# untitled.net
KiCad netlist of a schematic drawn in EAGLE
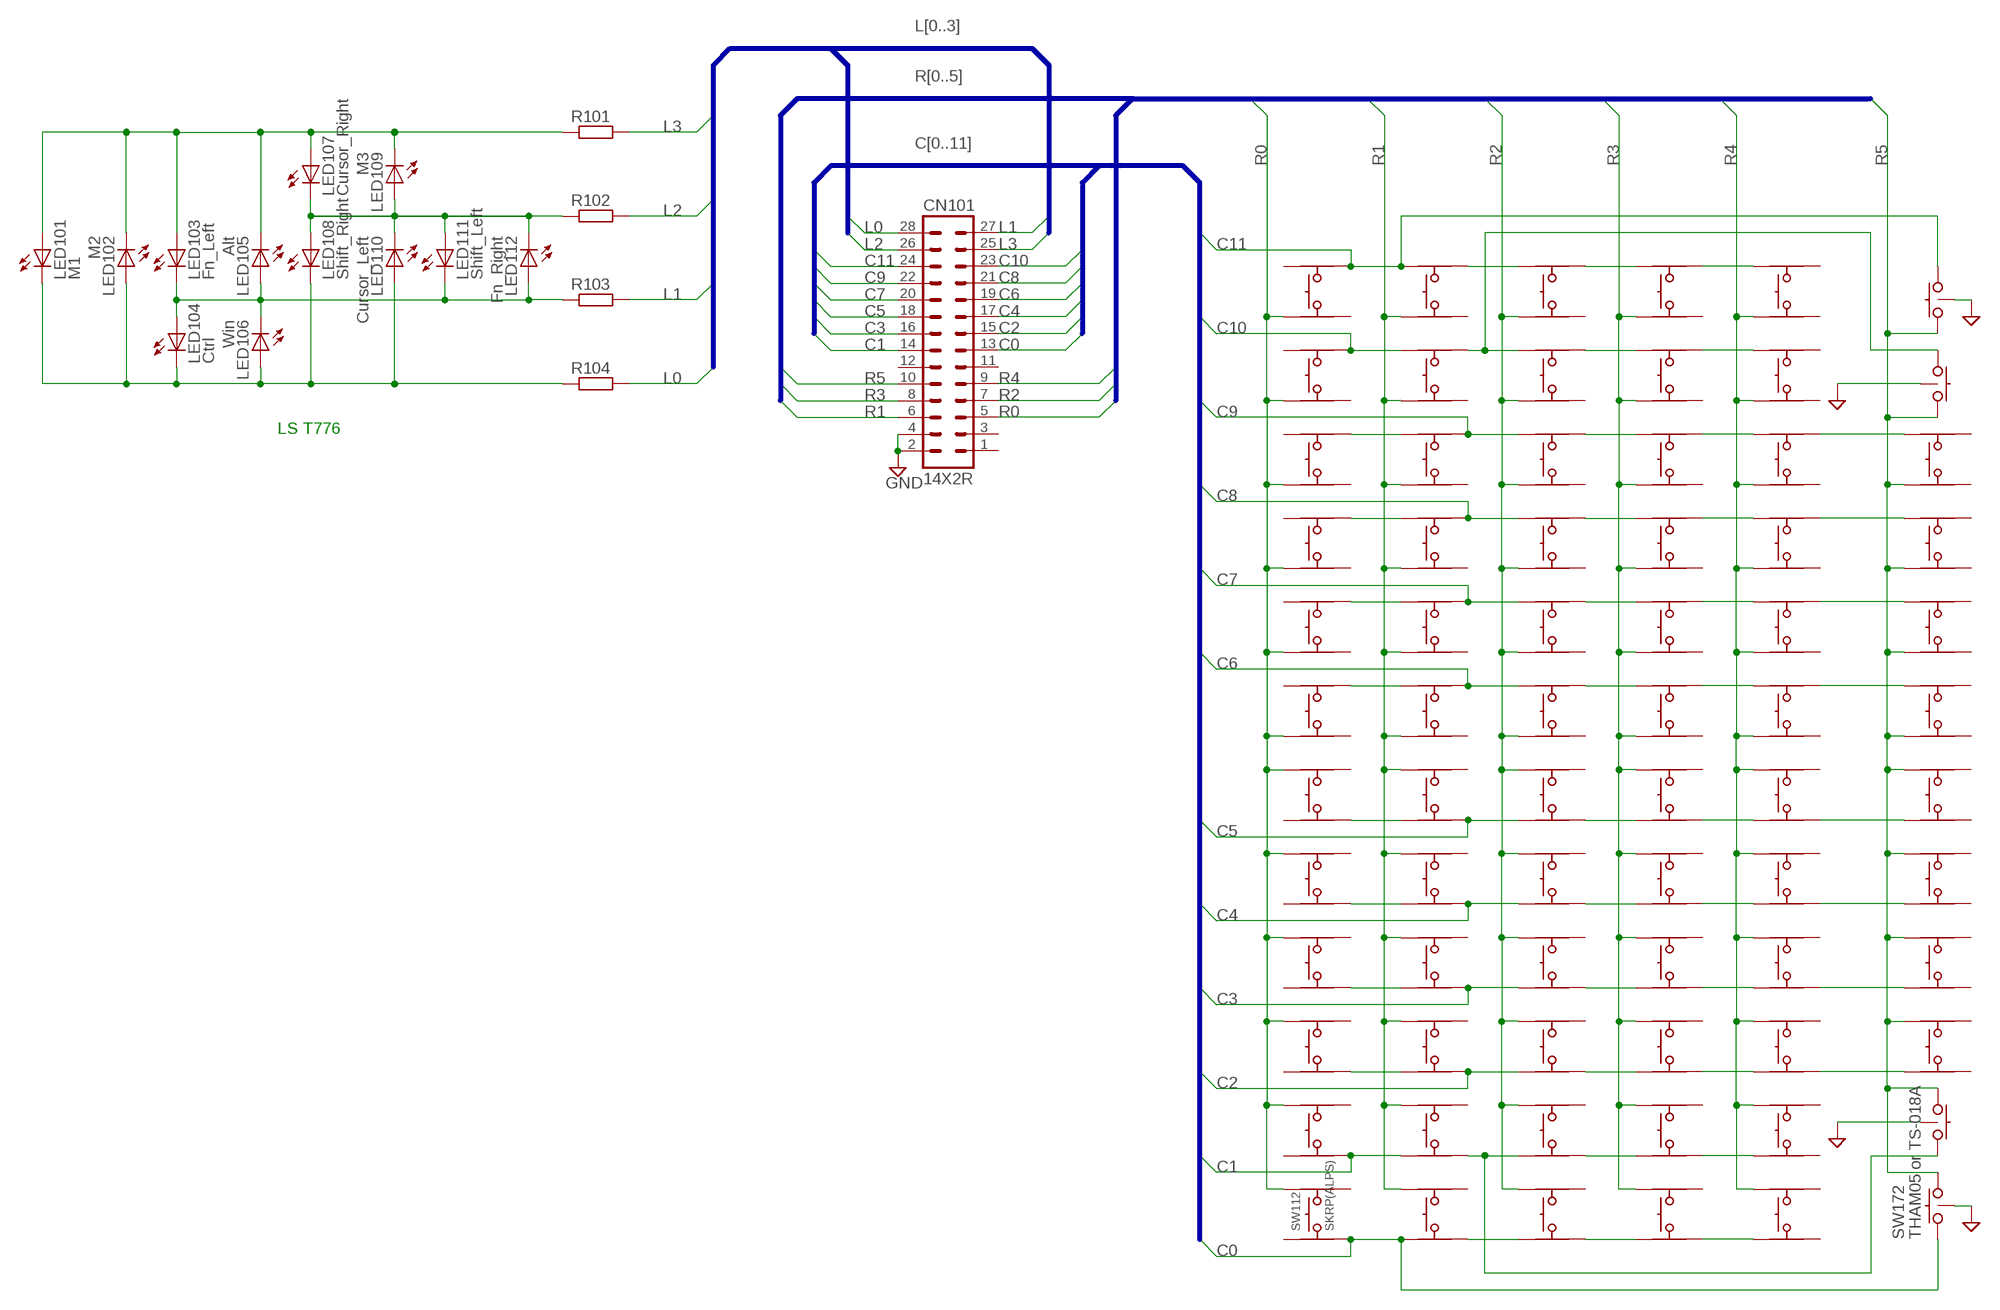
[diagram p0: schematic, sheet 1]

(export (version "E")
  (design (tool "Eeschema 10.0.6"))
  (components
    (comp (ref "CN101")
      (value "14X2R")
      (footprint "eagle-import:2MM_14X2_R")
      (libsource (lib "eagle-import") (part "14X2R"))
    )
    (comp (ref "LED101")
      (value "M1")
      (footprint "eagle-import:P-LCC-2-TOPLED-RG-WINDOW")
      (libsource (lib "eagle-import") (part "LEDP-LCC-2-BACK-W"))
    )
    (comp (ref "LED102")
      (value "M2")
      (footprint "eagle-import:P-LCC-2-TOPLED-RG-WINDOW")
      (libsource (lib "eagle-import") (part "LEDP-LCC-2-BACK-W"))
    )
    (comp (ref "LED103")
      (value "Fn_Left")
      (footprint "eagle-import:P-LCC-2-TOPLED-RG-WINDOW")
      (libsource (lib "eagle-import") (part "LEDP-LCC-2-BACK-W"))
    )
    (comp (ref "LED104")
      (value "Ctrl")
      (footprint "eagle-import:P-LCC-2-TOPLED-RG-WINDOW")
      (libsource (lib "eagle-import") (part "LEDP-LCC-2-BACK-W"))
    )
    (comp (ref "LED105")
      (value "Alt")
      (footprint "eagle-import:P-LCC-2-TOPLED-RG-WINDOW")
      (libsource (lib "eagle-import") (part "LEDP-LCC-2-BACK-W"))
    )
    (comp (ref "LED106")
      (value "Win")
      (footprint "eagle-import:P-LCC-2-TOPLED-RG-WINDOW")
      (libsource (lib "eagle-import") (part "LEDP-LCC-2-BACK-W"))
    )
    (comp (ref "LED107")
      (value "Cursor_Right")
      (footprint "eagle-import:P-LCC-2-TOPLED-RG-WINDOW")
      (libsource (lib "eagle-import") (part "LEDP-LCC-2-BACK-W"))
    )
    (comp (ref "LED108")
      (value "Shift_Right")
      (footprint "eagle-import:P-LCC-2-TOPLED-RG-WINDOW")
      (libsource (lib "eagle-import") (part "LEDP-LCC-2-BACK-W"))
    )
    (comp (ref "LED109")
      (value "M3")
      (footprint "eagle-import:P-LCC-2-TOPLED-RG-WINDOW")
      (libsource (lib "eagle-import") (part "LEDP-LCC-2-BACK-W"))
    )
    (comp (ref "LED110")
      (value "Cursor_Left")
      (footprint "eagle-import:P-LCC-2-TOPLED-RG-WINDOW")
      (libsource (lib "eagle-import") (part "LEDP-LCC-2-BACK-W"))
    )
    (comp (ref "LED111")
      (value "Shift_Left")
      (footprint "eagle-import:P-LCC-2-TOPLED-RG-WINDOW")
      (libsource (lib "eagle-import") (part "LEDP-LCC-2-BACK-W"))
    )
    (comp (ref "LED112")
      (value "Fn_Right")
      (footprint "eagle-import:P-LCC-2-TOPLED-RG-WINDOW")
      (libsource (lib "eagle-import") (part "LEDP-LCC-2-BACK-W"))
    )
    (comp (ref "R101")
      (value "R-EU_R0402-SS")
      (footprint "eagle-import:R0402-SS")
      (libsource (lib "eagle-import") (part "R-EU_R0402-SS"))
    )
    (comp (ref "R102")
      (value "R-EU_R0402-SS")
      (footprint "eagle-import:R0402-SS")
      (libsource (lib "eagle-import") (part "R-EU_R0402-SS"))
    )
    (comp (ref "R103")
      (value "R-EU_R0402-SS")
      (footprint "eagle-import:R0402-SS")
      (libsource (lib "eagle-import") (part "R-EU_R0402-SS"))
    )
    (comp (ref "R104")
      (value "R-EU_R0402-SS")
      (footprint "eagle-import:R0402-SS")
      (libsource (lib "eagle-import") (part "R-EU_R0402-SS"))
    )
    (comp (ref "SW101")
      (value "SW_4PTVAU10-025")
      (footprint "eagle-import:TVAU10-025")
      (libsource (lib "eagle-import") (part "SW_4PTVAU10-025"))
    )
    (comp (ref "SW102")
      (value "SW_4PTVAU10-025")
      (footprint "eagle-import:TVAU10-025")
      (libsource (lib "eagle-import") (part "SW_4PTVAU10-025"))
    )
    (comp (ref "SW103")
      (value "SW_4PTVAU10-025")
      (footprint "eagle-import:TVAU10-025")
      (libsource (lib "eagle-import") (part "SW_4PTVAU10-025"))
    )
    (comp (ref "SW104")
      (value "SW_4PTVAU10-025")
      (footprint "eagle-import:TVAU10-025")
      (libsource (lib "eagle-import") (part "SW_4PTVAU10-025"))
    )
    (comp (ref "SW105")
      (value "SW_4PTVAU10-025")
      (footprint "eagle-import:TVAU10-025")
      (libsource (lib "eagle-import") (part "SW_4PTVAU10-025"))
    )
    (comp (ref "SW106")
      (value "SW_4PTVAU10-025")
      (footprint "eagle-import:TVAU10-025")
      (libsource (lib "eagle-import") (part "SW_4PTVAU10-025"))
    )
    (comp (ref "SW107")
      (value "SW_4PTVAU10-025")
      (footprint "eagle-import:TVAU10-025")
      (libsource (lib "eagle-import") (part "SW_4PTVAU10-025"))
    )
    (comp (ref "SW108")
      (value "SW_4PTVAU10-025")
      (footprint "eagle-import:TVAU10-025")
      (libsource (lib "eagle-import") (part "SW_4PTVAU10-025"))
    )
    (comp (ref "SW109")
      (value "SW_4PTVAU10-025")
      (footprint "eagle-import:TVAU10-025")
      (libsource (lib "eagle-import") (part "SW_4PTVAU10-025"))
    )
    (comp (ref "SW110")
      (value "SW_4PTVAU10-025")
      (footprint "eagle-import:TVAU10-025")
      (libsource (lib "eagle-import") (part "SW_4PTVAU10-025"))
    )
    (comp (ref "SW111")
      (value "SW_4PTVAU10-025")
      (footprint "eagle-import:TVAU10-025")
      (libsource (lib "eagle-import") (part "SW_4PTVAU10-025"))
    )
    (comp (ref "SW112")
      (value "SKRP(ALPS)")
      (footprint "eagle-import:TVAU10-025")
      (libsource (lib "eagle-import") (part "SW_4PTVAU10-025"))
    )
    (comp (ref "SW113")
      (value "SW_4PTVAU10-025")
      (footprint "eagle-import:TVAU10-025")
      (libsource (lib "eagle-import") (part "SW_4PTVAU10-025"))
    )
    (comp (ref "SW114")
      (value "SW_4PTVAU10-025")
      (footprint "eagle-import:TVAU10-025")
      (libsource (lib "eagle-import") (part "SW_4PTVAU10-025"))
    )
    (comp (ref "SW115")
      (value "SW_4PTVAU10-025")
      (footprint "eagle-import:TVAU10-025")
      (libsource (lib "eagle-import") (part "SW_4PTVAU10-025"))
    )
    (comp (ref "SW116")
      (value "SW_4PTVAU10-025")
      (footprint "eagle-import:TVAU10-025")
      (libsource (lib "eagle-import") (part "SW_4PTVAU10-025"))
    )
    (comp (ref "SW117")
      (value "SW_4PTVAU10-025")
      (footprint "eagle-import:TVAU10-025")
      (libsource (lib "eagle-import") (part "SW_4PTVAU10-025"))
    )
    (comp (ref "SW118")
      (value "SW_4PTVAU10-025")
      (footprint "eagle-import:TVAU10-025")
      (libsource (lib "eagle-import") (part "SW_4PTVAU10-025"))
    )
    (comp (ref "SW119")
      (value "SW_4PTVAU10-025")
      (footprint "eagle-import:TVAU10-025")
      (libsource (lib "eagle-import") (part "SW_4PTVAU10-025"))
    )
    (comp (ref "SW120")
      (value "SW_4PTVAU10-025")
      (footprint "eagle-import:TVAU10-025")
      (libsource (lib "eagle-import") (part "SW_4PTVAU10-025"))
    )
    (comp (ref "SW121")
      (value "SW_4PTVAU10-025")
      (footprint "eagle-import:TVAU10-025")
      (libsource (lib "eagle-import") (part "SW_4PTVAU10-025"))
    )
    (comp (ref "SW122")
      (value "SW_4PTVAU10-025")
      (footprint "eagle-import:TVAU10-025")
      (libsource (lib "eagle-import") (part "SW_4PTVAU10-025"))
    )
    (comp (ref "SW123")
      (value "SW_4PTVAU10-025")
      (footprint "eagle-import:TVAU10-025")
      (libsource (lib "eagle-import") (part "SW_4PTVAU10-025"))
    )
    (comp (ref "SW124")
      (value "SW_4PTVAU10-025")
      (footprint "eagle-import:TVAU10-025")
      (libsource (lib "eagle-import") (part "SW_4PTVAU10-025"))
    )
    (comp (ref "SW125")
      (value "SW_4PTVAU10-025")
      (footprint "eagle-import:TVAU10-025")
      (libsource (lib "eagle-import") (part "SW_4PTVAU10-025"))
    )
    (comp (ref "SW126")
      (value "SW_4PTVAU10-025")
      (footprint "eagle-import:TVAU10-025")
      (libsource (lib "eagle-import") (part "SW_4PTVAU10-025"))
    )
    (comp (ref "SW127")
      (value "SW_4PTVAU10-025")
      (footprint "eagle-import:TVAU10-025")
      (libsource (lib "eagle-import") (part "SW_4PTVAU10-025"))
    )
    (comp (ref "SW128")
      (value "SW_4PTVAU10-025")
      (footprint "eagle-import:TVAU10-025")
      (libsource (lib "eagle-import") (part "SW_4PTVAU10-025"))
    )
    (comp (ref "SW129")
      (value "SW_4PTVAU10-025")
      (footprint "eagle-import:TVAU10-025")
      (libsource (lib "eagle-import") (part "SW_4PTVAU10-025"))
    )
    (comp (ref "SW130")
      (value "SW_4PTVAU10-025")
      (footprint "eagle-import:TVAU10-025")
      (libsource (lib "eagle-import") (part "SW_4PTVAU10-025"))
    )
    (comp (ref "SW131")
      (value "SW_4PTVAU10-025")
      (footprint "eagle-import:TVAU10-025")
      (libsource (lib "eagle-import") (part "SW_4PTVAU10-025"))
    )
    (comp (ref "SW132")
      (value "SW_4PTVAU10-025")
      (footprint "eagle-import:TVAU10-025")
      (libsource (lib "eagle-import") (part "SW_4PTVAU10-025"))
    )
    (comp (ref "SW133")
      (value "SW_4PTVAU10-025")
      (footprint "eagle-import:TVAU10-025")
      (libsource (lib "eagle-import") (part "SW_4PTVAU10-025"))
    )
    (comp (ref "SW134")
      (value "SW_4PTVAU10-025")
      (footprint "eagle-import:TVAU10-025")
      (libsource (lib "eagle-import") (part "SW_4PTVAU10-025"))
    )
    (comp (ref "SW135")
      (value "SW_4PTVAU10-025")
      (footprint "eagle-import:TVAU10-025")
      (libsource (lib "eagle-import") (part "SW_4PTVAU10-025"))
    )
    (comp (ref "SW136")
      (value "SW_4PTVAU10-025")
      (footprint "eagle-import:TVAU10-025")
      (libsource (lib "eagle-import") (part "SW_4PTVAU10-025"))
    )
    (comp (ref "SW137")
      (value "SW_4PTVAU10-025")
      (footprint "eagle-import:TVAU10-025")
      (libsource (lib "eagle-import") (part "SW_4PTVAU10-025"))
    )
    (comp (ref "SW138")
      (value "SW_4PTVAU10-025")
      (footprint "eagle-import:TVAU10-025")
      (libsource (lib "eagle-import") (part "SW_4PTVAU10-025"))
    )
    (comp (ref "SW139")
      (value "SW_4PTVAU10-025")
      (footprint "eagle-import:TVAU10-025")
      (libsource (lib "eagle-import") (part "SW_4PTVAU10-025"))
    )
    (comp (ref "SW140")
      (value "SW_4PTVAU10-025")
      (footprint "eagle-import:TVAU10-025")
      (libsource (lib "eagle-import") (part "SW_4PTVAU10-025"))
    )
    (comp (ref "SW141")
      (value "SW_4PTVAU10-025")
      (footprint "eagle-import:TVAU10-025")
      (libsource (lib "eagle-import") (part "SW_4PTVAU10-025"))
    )
    (comp (ref "SW142")
      (value "SW_4PTVAU10-025")
      (footprint "eagle-import:TVAU10-025")
      (libsource (lib "eagle-import") (part "SW_4PTVAU10-025"))
    )
    (comp (ref "SW143")
      (value "SW_4PTVAU10-025")
      (footprint "eagle-import:TVAU10-025")
      (libsource (lib "eagle-import") (part "SW_4PTVAU10-025"))
    )
    (comp (ref "SW144")
      (value "SW_4PTVAU10-025")
      (footprint "eagle-import:TVAU10-025")
      (libsource (lib "eagle-import") (part "SW_4PTVAU10-025"))
    )
    (comp (ref "SW145")
      (value "SW_4PTVAU10-025")
      (footprint "eagle-import:TVAU10-025")
      (libsource (lib "eagle-import") (part "SW_4PTVAU10-025"))
    )
    (comp (ref "SW146")
      (value "SW_4PTVAU10-025")
      (footprint "eagle-import:TVAU10-025")
      (libsource (lib "eagle-import") (part "SW_4PTVAU10-025"))
    )
    (comp (ref "SW147")
      (value "SW_4PTVAU10-025")
      (footprint "eagle-import:TVAU10-025")
      (libsource (lib "eagle-import") (part "SW_4PTVAU10-025"))
    )
    (comp (ref "SW148")
      (value "SW_4PTVAU10-025")
      (footprint "eagle-import:TVAU10-025")
      (libsource (lib "eagle-import") (part "SW_4PTVAU10-025"))
    )
    (comp (ref "SW149")
      (value "SW_4PTVAU10-025")
      (footprint "eagle-import:TVAU10-025")
      (libsource (lib "eagle-import") (part "SW_4PTVAU10-025"))
    )
    (comp (ref "SW150")
      (value "SW_4PTVAU10-025")
      (footprint "eagle-import:TVAU10-025")
      (libsource (lib "eagle-import") (part "SW_4PTVAU10-025"))
    )
    (comp (ref "SW151")
      (value "SW_4PTVAU10-025")
      (footprint "eagle-import:TVAU10-025")
      (libsource (lib "eagle-import") (part "SW_4PTVAU10-025"))
    )
    (comp (ref "SW152")
      (value "SW_4PTVAU10-025")
      (footprint "eagle-import:TVAU10-025")
      (libsource (lib "eagle-import") (part "SW_4PTVAU10-025"))
    )
    (comp (ref "SW153")
      (value "SW_4PTVAU10-025")
      (footprint "eagle-import:TVAU10-025")
      (libsource (lib "eagle-import") (part "SW_4PTVAU10-025"))
    )
    (comp (ref "SW154")
      (value "SW_4PTVAU10-025")
      (footprint "eagle-import:TVAU10-025")
      (libsource (lib "eagle-import") (part "SW_4PTVAU10-025"))
    )
    (comp (ref "SW155")
      (value "SW_4PTVAU10-025")
      (footprint "eagle-import:TVAU10-025")
      (libsource (lib "eagle-import") (part "SW_4PTVAU10-025"))
    )
    (comp (ref "SW156")
      (value "SW_4PTVAU10-025")
      (footprint "eagle-import:TVAU10-025")
      (libsource (lib "eagle-import") (part "SW_4PTVAU10-025"))
    )
    (comp (ref "SW157")
      (value "SW_4PTVAU10-025")
      (footprint "eagle-import:TVAU10-025")
      (libsource (lib "eagle-import") (part "SW_4PTVAU10-025"))
    )
    (comp (ref "SW158")
      (value "SW_4PTVAU10-025")
      (footprint "eagle-import:TVAU10-025")
      (libsource (lib "eagle-import") (part "SW_4PTVAU10-025"))
    )
    (comp (ref "SW159")
      (value "SW_4PTVAU10-025")
      (footprint "eagle-import:TVAU10-025")
      (libsource (lib "eagle-import") (part "SW_4PTVAU10-025"))
    )
    (comp (ref "SW160")
      (value "SW_4PTVAU10-025")
      (footprint "eagle-import:TVAU10-025")
      (libsource (lib "eagle-import") (part "SW_4PTVAU10-025"))
    )
    (comp (ref "SW161")
      (value "SW_WITH_EARTHX")
      (footprint "eagle-import:THAM05")
      (libsource (lib "eagle-import") (part "SW_WITH_EARTHX"))
    )
    (comp (ref "SW162")
      (value "SW_WITH_EARTHX")
      (footprint "eagle-import:THAM05")
      (libsource (lib "eagle-import") (part "SW_WITH_EARTHX"))
    )
    (comp (ref "SW163")
      (value "SW_4PTVAU10-025")
      (footprint "eagle-import:TVAU10-025")
      (libsource (lib "eagle-import") (part "SW_4PTVAU10-025"))
    )
    (comp (ref "SW164")
      (value "SW_4PTVAU10-025")
      (footprint "eagle-import:TVAU10-025")
      (libsource (lib "eagle-import") (part "SW_4PTVAU10-025"))
    )
    (comp (ref "SW165")
      (value "SW_4PTVAU10-025")
      (footprint "eagle-import:TVAU10-025")
      (libsource (lib "eagle-import") (part "SW_4PTVAU10-025"))
    )
    (comp (ref "SW166")
      (value "SW_4PTVAU10-025")
      (footprint "eagle-import:TVAU10-025")
      (libsource (lib "eagle-import") (part "SW_4PTVAU10-025"))
    )
    (comp (ref "SW167")
      (value "SW_4PTVAU10-025")
      (footprint "eagle-import:TVAU10-025")
      (libsource (lib "eagle-import") (part "SW_4PTVAU10-025"))
    )
    (comp (ref "SW168")
      (value "SW_4PTVAU10-025")
      (footprint "eagle-import:TVAU10-025")
      (libsource (lib "eagle-import") (part "SW_4PTVAU10-025"))
    )
    (comp (ref "SW169")
      (value "SW_4PTVAU10-025")
      (footprint "eagle-import:TVAU10-025")
      (libsource (lib "eagle-import") (part "SW_4PTVAU10-025"))
    )
    (comp (ref "SW170")
      (value "SW_4PTVAU10-025")
      (footprint "eagle-import:TVAU10-025")
      (libsource (lib "eagle-import") (part "SW_4PTVAU10-025"))
    )
    (comp (ref "SW171")
      (value "SW_WITH_EARTHX")
      (footprint "eagle-import:THAM05")
      (libsource (lib "eagle-import") (part "SW_WITH_EARTHX"))
    )
    (comp (ref "SW172")
      (value "THAM05 or TS-018A")
      (footprint "eagle-import:THAM05")
      (libsource (lib "eagle-import") (part "SW_WITH_EARTHX"))
    )
  )
  (nets
    (net (code "1") (name "/C0") (class "Default")
      (node (ref "CN101") (pin "13") (pinfunction "13_13") (pintype "passive"))
      (node (ref "SW112") (pin "P$2") (pinfunction "=A_P$2") (pintype "bidirectional"))
      (node (ref "SW124") (pin "P$1") (pinfunction "A_P$1") (pintype "bidirectional"))
      (node (ref "SW172") (pin "P$1") (pinfunction "P$1_P$1") (pintype "passive"))
    )
    (net (code "2") (name "/C1") (class "Default")
      (node (ref "CN101") (pin "14") (pinfunction "14_14") (pintype "passive"))
      (node (ref "SW111") (pin "P$2") (pinfunction "=A_P$2") (pintype "bidirectional"))
      (node (ref "SW123") (pin "P$1") (pinfunction "A_P$1") (pintype "bidirectional"))
    )
    (net (code "3") (name "/C2") (class "Default")
      (node (ref "CN101") (pin "15") (pinfunction "15_15") (pintype "passive"))
      (node (ref "SW122") (pin "P$2") (pinfunction "=A_P$2") (pintype "bidirectional"))
      (node (ref "SW134") (pin "P$1") (pinfunction "A_P$1") (pintype "bidirectional"))
    )
    (net (code "4") (name "/C3") (class "Default")
      (node (ref "CN101") (pin "16") (pinfunction "16_16") (pintype "passive"))
      (node (ref "SW121") (pin "P$2") (pinfunction "=A_P$2") (pintype "bidirectional"))
      (node (ref "SW133") (pin "P$1") (pinfunction "A_P$1") (pintype "bidirectional"))
    )
    (net (code "5") (name "/C4") (class "Default")
      (node (ref "CN101") (pin "17") (pinfunction "17_17") (pintype "passive"))
      (node (ref "SW120") (pin "P$2") (pinfunction "=A_P$2") (pintype "bidirectional"))
      (node (ref "SW132") (pin "P$1") (pinfunction "A_P$1") (pintype "bidirectional"))
    )
    (net (code "6") (name "/C5") (class "Default")
      (node (ref "CN101") (pin "18") (pinfunction "18_18") (pintype "passive"))
      (node (ref "SW119") (pin "P$2") (pinfunction "=A_P$2") (pintype "bidirectional"))
      (node (ref "SW131") (pin "P$1") (pinfunction "A_P$1") (pintype "bidirectional"))
    )
    (net (code "7") (name "/C6") (class "Default")
      (node (ref "CN101") (pin "19") (pinfunction "19_19") (pintype "passive"))
      (node (ref "SW118") (pin "P$4") (pinfunction "=B_P$4") (pintype "bidirectional"))
      (node (ref "SW130") (pin "P$3") (pinfunction "B_P$3") (pintype "bidirectional"))
    )
    (net (code "8") (name "/C7") (class "Default")
      (node (ref "CN101") (pin "20") (pinfunction "20_20") (pintype "passive"))
      (node (ref "SW117") (pin "P$4") (pinfunction "=B_P$4") (pintype "bidirectional"))
      (node (ref "SW129") (pin "P$3") (pinfunction "B_P$3") (pintype "bidirectional"))
    )
    (net (code "9") (name "/C8") (class "Default")
      (node (ref "CN101") (pin "21") (pinfunction "21_21") (pintype "passive"))
      (node (ref "SW116") (pin "P$4") (pinfunction "=B_P$4") (pintype "bidirectional"))
      (node (ref "SW128") (pin "P$3") (pinfunction "B_P$3") (pintype "bidirectional"))
    )
    (net (code "10") (name "/C9") (class "Default")
      (node (ref "CN101") (pin "22") (pinfunction "22_22") (pintype "passive"))
      (node (ref "SW115") (pin "P$4") (pinfunction "=B_P$4") (pintype "bidirectional"))
      (node (ref "SW127") (pin "P$3") (pinfunction "B_P$3") (pintype "bidirectional"))
    )
    (net (code "11") (name "/C10") (class "Default")
      (node (ref "CN101") (pin "23") (pinfunction "23_23") (pintype "passive"))
      (node (ref "SW102") (pin "P$4") (pinfunction "=B_P$4") (pintype "bidirectional"))
      (node (ref "SW114") (pin "P$3") (pinfunction "B_P$3") (pintype "bidirectional"))
    )
    (net (code "12") (name "/C11") (class "Default")
      (node (ref "CN101") (pin "24") (pinfunction "24_24") (pintype "passive"))
      (node (ref "SW101") (pin "P$4") (pinfunction "=B_P$4") (pintype "bidirectional"))
      (node (ref "SW113") (pin "P$3") (pinfunction "B_P$3") (pintype "bidirectional"))
      (node (ref "SW161") (pin "P$2") (pinfunction "P$2_P$2") (pintype "passive"))
    )
    (net (code "14") (name "/L0") (class "Default")
      (node (ref "CN101") (pin "28") (pinfunction "28_28") (pintype "passive"))
      (node (ref "R104") (pin "2") (pinfunction "2_2") (pintype "passive"))
    )
    (net (code "15") (name "/L1") (class "Default")
      (node (ref "CN101") (pin "27") (pinfunction "27_27") (pintype "passive"))
      (node (ref "R103") (pin "2") (pinfunction "2_2") (pintype "passive"))
    )
    (net (code "16") (name "/L2") (class "Default")
      (node (ref "CN101") (pin "26") (pinfunction "26_26") (pintype "passive"))
      (node (ref "R102") (pin "2") (pinfunction "2_2") (pintype "passive"))
    )
    (net (code "17") (name "/L3") (class "Default")
      (node (ref "CN101") (pin "25") (pinfunction "25_25") (pintype "passive"))
      (node (ref "R101") (pin "2") (pinfunction "2_2") (pintype "passive"))
    )
    (net (code "19") (name "/R0") (class "Default")
      (node (ref "CN101") (pin "5") (pinfunction "5_5") (pintype "passive"))
      (node (ref "SW101") (pin "P$1") (pinfunction "A_P$1") (pintype "bidirectional"))
      (node (ref "SW102") (pin "P$1") (pinfunction "A_P$1") (pintype "bidirectional"))
      (node (ref "SW103") (pin "P$1") (pinfunction "A_P$1") (pintype "bidirectional"))
      (node (ref "SW104") (pin "P$1") (pinfunction "A_P$1") (pintype "bidirectional"))
      (node (ref "SW105") (pin "P$1") (pinfunction "A_P$1") (pintype "bidirectional"))
      (node (ref "SW106") (pin "P$1") (pinfunction "A_P$1") (pintype "bidirectional"))
      (node (ref "SW107") (pin "P$3") (pinfunction "B_P$3") (pintype "bidirectional"))
      (node (ref "SW108") (pin "P$3") (pinfunction "B_P$3") (pintype "bidirectional"))
      (node (ref "SW109") (pin "P$3") (pinfunction "B_P$3") (pintype "bidirectional"))
      (node (ref "SW110") (pin "P$3") (pinfunction "B_P$3") (pintype "bidirectional"))
      (node (ref "SW111") (pin "P$3") (pinfunction "B_P$3") (pintype "bidirectional"))
      (node (ref "SW112") (pin "P$3") (pinfunction "B_P$3") (pintype "bidirectional"))
    )
    (net (code "20") (name "/R1") (class "Default")
      (node (ref "CN101") (pin "6") (pinfunction "6_6") (pintype "passive"))
      (node (ref "SW113") (pin "P$1") (pinfunction "A_P$1") (pintype "bidirectional"))
      (node (ref "SW114") (pin "P$1") (pinfunction "A_P$1") (pintype "bidirectional"))
      (node (ref "SW115") (pin "P$1") (pinfunction "A_P$1") (pintype "bidirectional"))
      (node (ref "SW116") (pin "P$1") (pinfunction "A_P$1") (pintype "bidirectional"))
      (node (ref "SW117") (pin "P$1") (pinfunction "A_P$1") (pintype "bidirectional"))
      (node (ref "SW118") (pin "P$1") (pinfunction "A_P$1") (pintype "bidirectional"))
      (node (ref "SW119") (pin "P$3") (pinfunction "B_P$3") (pintype "bidirectional"))
      (node (ref "SW120") (pin "P$3") (pinfunction "B_P$3") (pintype "bidirectional"))
      (node (ref "SW121") (pin "P$3") (pinfunction "B_P$3") (pintype "bidirectional"))
      (node (ref "SW122") (pin "P$3") (pinfunction "B_P$3") (pintype "bidirectional"))
      (node (ref "SW123") (pin "P$3") (pinfunction "B_P$3") (pintype "bidirectional"))
      (node (ref "SW124") (pin "P$3") (pinfunction "B_P$3") (pintype "bidirectional"))
    )
    (net (code "21") (name "/R2") (class "Default")
      (node (ref "CN101") (pin "7") (pinfunction "7_7") (pintype "passive"))
      (node (ref "SW125") (pin "P$1") (pinfunction "A_P$1") (pintype "bidirectional"))
      (node (ref "SW126") (pin "P$1") (pinfunction "A_P$1") (pintype "bidirectional"))
      (node (ref "SW127") (pin "P$1") (pinfunction "A_P$1") (pintype "bidirectional"))
      (node (ref "SW128") (pin "P$1") (pinfunction "A_P$1") (pintype "bidirectional"))
      (node (ref "SW129") (pin "P$1") (pinfunction "A_P$1") (pintype "bidirectional"))
      (node (ref "SW130") (pin "P$1") (pinfunction "A_P$1") (pintype "bidirectional"))
      (node (ref "SW131") (pin "P$3") (pinfunction "B_P$3") (pintype "bidirectional"))
      (node (ref "SW132") (pin "P$3") (pinfunction "B_P$3") (pintype "bidirectional"))
      (node (ref "SW133") (pin "P$3") (pinfunction "B_P$3") (pintype "bidirectional"))
      (node (ref "SW134") (pin "P$3") (pinfunction "B_P$3") (pintype "bidirectional"))
      (node (ref "SW135") (pin "P$3") (pinfunction "B_P$3") (pintype "bidirectional"))
      (node (ref "SW136") (pin "P$3") (pinfunction "B_P$3") (pintype "bidirectional"))
    )
    (net (code "22") (name "/R3") (class "Default")
      (node (ref "CN101") (pin "8") (pinfunction "8_8") (pintype "passive"))
      (node (ref "SW137") (pin "P$1") (pinfunction "A_P$1") (pintype "bidirectional"))
      (node (ref "SW138") (pin "P$1") (pinfunction "A_P$1") (pintype "bidirectional"))
      (node (ref "SW139") (pin "P$1") (pinfunction "A_P$1") (pintype "bidirectional"))
      (node (ref "SW140") (pin "P$1") (pinfunction "A_P$1") (pintype "bidirectional"))
      (node (ref "SW141") (pin "P$1") (pinfunction "A_P$1") (pintype "bidirectional"))
      (node (ref "SW142") (pin "P$1") (pinfunction "A_P$1") (pintype "bidirectional"))
      (node (ref "SW143") (pin "P$3") (pinfunction "B_P$3") (pintype "bidirectional"))
      (node (ref "SW144") (pin "P$3") (pinfunction "B_P$3") (pintype "bidirectional"))
      (node (ref "SW145") (pin "P$3") (pinfunction "B_P$3") (pintype "bidirectional"))
      (node (ref "SW146") (pin "P$3") (pinfunction "B_P$3") (pintype "bidirectional"))
      (node (ref "SW147") (pin "P$3") (pinfunction "B_P$3") (pintype "bidirectional"))
      (node (ref "SW148") (pin "P$3") (pinfunction "B_P$3") (pintype "bidirectional"))
    )
    (net (code "23") (name "/R4") (class "Default")
      (node (ref "CN101") (pin "9") (pinfunction "9_9") (pintype "passive"))
      (node (ref "SW149") (pin "P$1") (pinfunction "A_P$1") (pintype "bidirectional"))
      (node (ref "SW150") (pin "P$1") (pinfunction "A_P$1") (pintype "bidirectional"))
      (node (ref "SW151") (pin "P$1") (pinfunction "A_P$1") (pintype "bidirectional"))
      (node (ref "SW152") (pin "P$1") (pinfunction "A_P$1") (pintype "bidirectional"))
      (node (ref "SW153") (pin "P$1") (pinfunction "A_P$1") (pintype "bidirectional"))
      (node (ref "SW154") (pin "P$1") (pinfunction "A_P$1") (pintype "bidirectional"))
      (node (ref "SW155") (pin "P$3") (pinfunction "B_P$3") (pintype "bidirectional"))
      (node (ref "SW156") (pin "P$3") (pinfunction "B_P$3") (pintype "bidirectional"))
      (node (ref "SW157") (pin "P$3") (pinfunction "B_P$3") (pintype "bidirectional"))
      (node (ref "SW158") (pin "P$3") (pinfunction "B_P$3") (pintype "bidirectional"))
      (node (ref "SW159") (pin "P$3") (pinfunction "B_P$3") (pintype "bidirectional"))
      (node (ref "SW160") (pin "P$3") (pinfunction "B_P$3") (pintype "bidirectional"))
    )
    (net (code "24") (name "/R5") (class "Default")
      (node (ref "CN101") (pin "10") (pinfunction "10_10") (pintype "passive"))
      (node (ref "SW161") (pin "P$1") (pinfunction "P$1_P$1") (pintype "passive"))
      (node (ref "SW162") (pin "P$2") (pinfunction "P$2_P$2") (pintype "passive"))
      (node (ref "SW163") (pin "P$1") (pinfunction "A_P$1") (pintype "bidirectional"))
      (node (ref "SW164") (pin "P$1") (pinfunction "A_P$1") (pintype "bidirectional"))
      (node (ref "SW165") (pin "P$1") (pinfunction "A_P$1") (pintype "bidirectional"))
      (node (ref "SW166") (pin "P$1") (pinfunction "A_P$1") (pintype "bidirectional"))
      (node (ref "SW167") (pin "P$3") (pinfunction "B_P$3") (pintype "bidirectional"))
      (node (ref "SW168") (pin "P$3") (pinfunction "B_P$3") (pintype "bidirectional"))
      (node (ref "SW169") (pin "P$3") (pinfunction "B_P$3") (pintype "bidirectional"))
      (node (ref "SW170") (pin "P$3") (pinfunction "B_P$3") (pintype "bidirectional"))
      (node (ref "SW171") (pin "P$1") (pinfunction "P$1_P$1") (pintype "passive"))
      (node (ref "SW172") (pin "P$2") (pinfunction "P$2_P$2") (pintype "passive"))
    )
    (net (code "26") (name "GND") (class "Default")
      (node (ref "CN101") (pin "2") (pinfunction "2_2") (pintype "passive"))
      (node (ref "CN101") (pin "4") (pinfunction "4_4") (pintype "passive"))
      (node (ref "SW161") (pin "S1") (pinfunction "P$3_S1") (pintype "passive"))
      (node (ref "SW161") (pin "S2") (pinfunction "P$3_S2") (pintype "passive"))
      (node (ref "SW161") (pin "S3") (pinfunction "P$3_S3") (pintype "passive"))
      (node (ref "SW161") (pin "S4") (pinfunction "P$3_S4") (pintype "passive"))
      (node (ref "SW161") (pin "S5") (pinfunction "P$3_S5") (pintype "passive"))
      (node (ref "SW162") (pin "S1") (pinfunction "P$3_S1") (pintype "passive"))
      (node (ref "SW162") (pin "S2") (pinfunction "P$3_S2") (pintype "passive"))
      (node (ref "SW162") (pin "S3") (pinfunction "P$3_S3") (pintype "passive"))
      (node (ref "SW162") (pin "S4") (pinfunction "P$3_S4") (pintype "passive"))
      (node (ref "SW162") (pin "S5") (pinfunction "P$3_S5") (pintype "passive"))
      (node (ref "SW171") (pin "S1") (pinfunction "P$3_S1") (pintype "passive"))
      (node (ref "SW171") (pin "S2") (pinfunction "P$3_S2") (pintype "passive"))
      (node (ref "SW171") (pin "S3") (pinfunction "P$3_S3") (pintype "passive"))
      (node (ref "SW171") (pin "S4") (pinfunction "P$3_S4") (pintype "passive"))
      (node (ref "SW171") (pin "S5") (pinfunction "P$3_S5") (pintype "passive"))
      (node (ref "SW172") (pin "S1") (pinfunction "P$3_S1") (pintype "passive"))
      (node (ref "SW172") (pin "S2") (pinfunction "P$3_S2") (pintype "passive"))
      (node (ref "SW172") (pin "S3") (pinfunction "P$3_S3") (pintype "passive"))
      (node (ref "SW172") (pin "S4") (pinfunction "P$3_S4") (pintype "passive"))
      (node (ref "SW172") (pin "S5") (pinfunction "P$3_S5") (pintype "passive"))
    )
    (net (code "27") (name "Net-(LED101-PadA)") (class "Default")
      (node (ref "LED101") (pin "A") (pinfunction "A_A") (pintype "passive"))
      (node (ref "LED102") (pin "C") (pinfunction "C_C") (pintype "passive"))
      (node (ref "LED103") (pin "A") (pinfunction "A_A") (pintype "passive"))
      (node (ref "LED105") (pin "C") (pinfunction "C_C") (pintype "passive"))
      (node (ref "LED107") (pin "A") (pinfunction "A_A") (pintype "passive"))
      (node (ref "LED109") (pin "C") (pinfunction "C_C") (pintype "passive"))
      (node (ref "R101") (pin "1") (pinfunction "1_1") (pintype "passive"))
    )
    (net (code "28") (name "Net-(LED101-PadC)") (class "Default")
      (node (ref "LED101") (pin "C") (pinfunction "C_C") (pintype "passive"))
      (node (ref "LED102") (pin "A") (pinfunction "A_A") (pintype "passive"))
      (node (ref "LED104") (pin "C") (pinfunction "C_C") (pintype "passive"))
      (node (ref "LED106") (pin "A") (pinfunction "A_A") (pintype "passive"))
      (node (ref "LED108") (pin "C") (pinfunction "C_C") (pintype "passive"))
      (node (ref "LED110") (pin "A") (pinfunction "A_A") (pintype "passive"))
      (node (ref "R104") (pin "1") (pinfunction "1_1") (pintype "passive"))
    )
    (net (code "29") (name "Net-(LED103-PadC)") (class "Default")
      (node (ref "LED103") (pin "C") (pinfunction "C_C") (pintype "passive"))
      (node (ref "LED104") (pin "A") (pinfunction "A_A") (pintype "passive"))
      (node (ref "LED105") (pin "A") (pinfunction "A_A") (pintype "passive"))
      (node (ref "LED106") (pin "C") (pinfunction "C_C") (pintype "passive"))
      (node (ref "LED111") (pin "C") (pinfunction "C_C") (pintype "passive"))
      (node (ref "LED112") (pin "A") (pinfunction "A_A") (pintype "passive"))
      (node (ref "R103") (pin "1") (pinfunction "1_1") (pintype "passive"))
    )
    (net (code "30") (name "Net-(LED107-PadC)") (class "Default")
      (node (ref "LED107") (pin "C") (pinfunction "C_C") (pintype "passive"))
      (node (ref "LED108") (pin "A") (pinfunction "A_A") (pintype "passive"))
      (node (ref "LED109") (pin "A") (pinfunction "A_A") (pintype "passive"))
      (node (ref "LED110") (pin "C") (pinfunction "C_C") (pintype "passive"))
      (node (ref "LED111") (pin "A") (pinfunction "A_A") (pintype "passive"))
      (node (ref "LED112") (pin "C") (pinfunction "C_C") (pintype "passive"))
      (node (ref "R102") (pin "1") (pinfunction "1_1") (pintype "passive"))
    )
    (net (code "31") (name "Net-(SW103-=B)") (class "Default")
      (node (ref "SW103") (pin "P$4") (pinfunction "=B_P$4") (pintype "bidirectional"))
      (node (ref "SW115") (pin "P$3") (pinfunction "B_P$3") (pintype "bidirectional"))
    )
    (net (code "32") (name "Net-(SW104-=B)") (class "Default")
      (node (ref "SW104") (pin "P$4") (pinfunction "=B_P$4") (pintype "bidirectional"))
      (node (ref "SW116") (pin "P$3") (pinfunction "B_P$3") (pintype "bidirectional"))
    )
    (net (code "33") (name "Net-(SW105-=B)") (class "Default")
      (node (ref "SW105") (pin "P$4") (pinfunction "=B_P$4") (pintype "bidirectional"))
      (node (ref "SW117") (pin "P$3") (pinfunction "B_P$3") (pintype "bidirectional"))
    )
    (net (code "34") (name "Net-(SW106-=B)") (class "Default")
      (node (ref "SW106") (pin "P$4") (pinfunction "=B_P$4") (pintype "bidirectional"))
      (node (ref "SW118") (pin "P$3") (pinfunction "B_P$3") (pintype "bidirectional"))
    )
    (net (code "35") (name "Net-(SW107-=A)") (class "Default")
      (node (ref "SW107") (pin "P$2") (pinfunction "=A_P$2") (pintype "bidirectional"))
      (node (ref "SW119") (pin "P$1") (pinfunction "A_P$1") (pintype "bidirectional"))
    )
    (net (code "36") (name "Net-(SW108-=A)") (class "Default")
      (node (ref "SW108") (pin "P$2") (pinfunction "=A_P$2") (pintype "bidirectional"))
      (node (ref "SW120") (pin "P$1") (pinfunction "A_P$1") (pintype "bidirectional"))
    )
    (net (code "37") (name "Net-(SW109-=A)") (class "Default")
      (node (ref "SW109") (pin "P$2") (pinfunction "=A_P$2") (pintype "bidirectional"))
      (node (ref "SW121") (pin "P$1") (pinfunction "A_P$1") (pintype "bidirectional"))
    )
    (net (code "38") (name "Net-(SW110-=A)") (class "Default")
      (node (ref "SW110") (pin "P$2") (pinfunction "=A_P$2") (pintype "bidirectional"))
      (node (ref "SW122") (pin "P$1") (pinfunction "A_P$1") (pintype "bidirectional"))
    )
    (net (code "39") (name "Net-(SW113-=B)") (class "Default")
      (node (ref "SW113") (pin "P$4") (pinfunction "=B_P$4") (pintype "bidirectional"))
      (node (ref "SW125") (pin "P$3") (pinfunction "B_P$3") (pintype "bidirectional"))
    )
    (net (code "40") (name "Net-(SW114-=B)") (class "Default")
      (node (ref "SW114") (pin "P$4") (pinfunction "=B_P$4") (pintype "bidirectional"))
      (node (ref "SW126") (pin "P$3") (pinfunction "B_P$3") (pintype "bidirectional"))
      (node (ref "SW162") (pin "P$1") (pinfunction "P$1_P$1") (pintype "passive"))
    )
    (net (code "41") (name "Net-(SW123-=A)") (class "Default")
      (node (ref "SW123") (pin "P$2") (pinfunction "=A_P$2") (pintype "bidirectional"))
      (node (ref "SW135") (pin "P$1") (pinfunction "A_P$1") (pintype "bidirectional"))
      (node (ref "SW171") (pin "P$2") (pinfunction "P$2_P$2") (pintype "passive"))
    )
    (net (code "42") (name "Net-(SW124-=A)") (class "Default")
      (node (ref "SW124") (pin "P$2") (pinfunction "=A_P$2") (pintype "bidirectional"))
      (node (ref "SW136") (pin "P$1") (pinfunction "A_P$1") (pintype "bidirectional"))
    )
    (net (code "43") (name "Net-(SW125-=B)") (class "Default")
      (node (ref "SW125") (pin "P$4") (pinfunction "=B_P$4") (pintype "bidirectional"))
      (node (ref "SW137") (pin "P$3") (pinfunction "B_P$3") (pintype "bidirectional"))
    )
    (net (code "44") (name "Net-(SW126-=B)") (class "Default")
      (node (ref "SW126") (pin "P$4") (pinfunction "=B_P$4") (pintype "bidirectional"))
      (node (ref "SW138") (pin "P$3") (pinfunction "B_P$3") (pintype "bidirectional"))
    )
    (net (code "45") (name "Net-(SW127-=B)") (class "Default")
      (node (ref "SW127") (pin "P$4") (pinfunction "=B_P$4") (pintype "bidirectional"))
      (node (ref "SW139") (pin "P$3") (pinfunction "B_P$3") (pintype "bidirectional"))
    )
    (net (code "46") (name "Net-(SW128-=B)") (class "Default")
      (node (ref "SW128") (pin "P$4") (pinfunction "=B_P$4") (pintype "bidirectional"))
      (node (ref "SW140") (pin "P$3") (pinfunction "B_P$3") (pintype "bidirectional"))
    )
    (net (code "47") (name "Net-(SW129-=B)") (class "Default")
      (node (ref "SW129") (pin "P$4") (pinfunction "=B_P$4") (pintype "bidirectional"))
      (node (ref "SW141") (pin "P$3") (pinfunction "B_P$3") (pintype "bidirectional"))
    )
    (net (code "48") (name "Net-(SW130-=B)") (class "Default")
      (node (ref "SW130") (pin "P$4") (pinfunction "=B_P$4") (pintype "bidirectional"))
      (node (ref "SW142") (pin "P$3") (pinfunction "B_P$3") (pintype "bidirectional"))
    )
    (net (code "49") (name "Net-(SW131-=A)") (class "Default")
      (node (ref "SW131") (pin "P$2") (pinfunction "=A_P$2") (pintype "bidirectional"))
      (node (ref "SW143") (pin "P$1") (pinfunction "A_P$1") (pintype "bidirectional"))
    )
    (net (code "50") (name "Net-(SW132-=A)") (class "Default")
      (node (ref "SW132") (pin "P$2") (pinfunction "=A_P$2") (pintype "bidirectional"))
      (node (ref "SW144") (pin "P$1") (pinfunction "A_P$1") (pintype "bidirectional"))
    )
    (net (code "51") (name "Net-(SW133-=A)") (class "Default")
      (node (ref "SW133") (pin "P$2") (pinfunction "=A_P$2") (pintype "bidirectional"))
      (node (ref "SW145") (pin "P$1") (pinfunction "A_P$1") (pintype "bidirectional"))
    )
    (net (code "52") (name "Net-(SW134-=A)") (class "Default")
      (node (ref "SW134") (pin "P$2") (pinfunction "=A_P$2") (pintype "bidirectional"))
      (node (ref "SW146") (pin "P$1") (pinfunction "A_P$1") (pintype "bidirectional"))
    )
    (net (code "53") (name "Net-(SW135-=A)") (class "Default")
      (node (ref "SW135") (pin "P$2") (pinfunction "=A_P$2") (pintype "bidirectional"))
      (node (ref "SW147") (pin "P$1") (pinfunction "A_P$1") (pintype "bidirectional"))
    )
    (net (code "54") (name "Net-(SW136-=A)") (class "Default")
      (node (ref "SW136") (pin "P$2") (pinfunction "=A_P$2") (pintype "bidirectional"))
      (node (ref "SW148") (pin "P$1") (pinfunction "A_P$1") (pintype "bidirectional"))
    )
    (net (code "55") (name "Net-(SW137-=B)") (class "Default")
      (node (ref "SW137") (pin "P$4") (pinfunction "=B_P$4") (pintype "bidirectional"))
      (node (ref "SW149") (pin "P$3") (pinfunction "B_P$3") (pintype "bidirectional"))
    )
    (net (code "56") (name "Net-(SW138-=B)") (class "Default")
      (node (ref "SW138") (pin "P$4") (pinfunction "=B_P$4") (pintype "bidirectional"))
      (node (ref "SW150") (pin "P$3") (pinfunction "B_P$3") (pintype "bidirectional"))
    )
    (net (code "57") (name "Net-(SW139-=B)") (class "Default")
      (node (ref "SW139") (pin "P$4") (pinfunction "=B_P$4") (pintype "bidirectional"))
      (node (ref "SW151") (pin "P$3") (pinfunction "B_P$3") (pintype "bidirectional"))
    )
    (net (code "58") (name "Net-(SW140-=B)") (class "Default")
      (node (ref "SW140") (pin "P$4") (pinfunction "=B_P$4") (pintype "bidirectional"))
      (node (ref "SW152") (pin "P$3") (pinfunction "B_P$3") (pintype "bidirectional"))
    )
    (net (code "59") (name "Net-(SW141-=B)") (class "Default")
      (node (ref "SW141") (pin "P$4") (pinfunction "=B_P$4") (pintype "bidirectional"))
      (node (ref "SW153") (pin "P$3") (pinfunction "B_P$3") (pintype "bidirectional"))
    )
    (net (code "60") (name "Net-(SW142-=B)") (class "Default")
      (node (ref "SW142") (pin "P$4") (pinfunction "=B_P$4") (pintype "bidirectional"))
      (node (ref "SW154") (pin "P$3") (pinfunction "B_P$3") (pintype "bidirectional"))
    )
    (net (code "61") (name "Net-(SW143-=A)") (class "Default")
      (node (ref "SW143") (pin "P$2") (pinfunction "=A_P$2") (pintype "bidirectional"))
      (node (ref "SW155") (pin "P$1") (pinfunction "A_P$1") (pintype "bidirectional"))
    )
    (net (code "62") (name "Net-(SW144-=A)") (class "Default")
      (node (ref "SW144") (pin "P$2") (pinfunction "=A_P$2") (pintype "bidirectional"))
      (node (ref "SW156") (pin "P$1") (pinfunction "A_P$1") (pintype "bidirectional"))
    )
    (net (code "63") (name "Net-(SW145-=A)") (class "Default")
      (node (ref "SW145") (pin "P$2") (pinfunction "=A_P$2") (pintype "bidirectional"))
      (node (ref "SW157") (pin "P$1") (pinfunction "A_P$1") (pintype "bidirectional"))
    )
    (net (code "64") (name "Net-(SW146-=A)") (class "Default")
      (node (ref "SW146") (pin "P$2") (pinfunction "=A_P$2") (pintype "bidirectional"))
      (node (ref "SW158") (pin "P$1") (pinfunction "A_P$1") (pintype "bidirectional"))
    )
    (net (code "65") (name "Net-(SW147-=A)") (class "Default")
      (node (ref "SW147") (pin "P$2") (pinfunction "=A_P$2") (pintype "bidirectional"))
      (node (ref "SW159") (pin "P$1") (pinfunction "A_P$1") (pintype "bidirectional"))
    )
    (net (code "66") (name "Net-(SW148-=A)") (class "Default")
      (node (ref "SW148") (pin "P$2") (pinfunction "=A_P$2") (pintype "bidirectional"))
      (node (ref "SW160") (pin "P$1") (pinfunction "A_P$1") (pintype "bidirectional"))
    )
    (net (code "67") (name "Net-(SW151-=B)") (class "Default")
      (node (ref "SW151") (pin "P$4") (pinfunction "=B_P$4") (pintype "bidirectional"))
      (node (ref "SW163") (pin "P$3") (pinfunction "B_P$3") (pintype "bidirectional"))
    )
    (net (code "68") (name "Net-(SW152-=B)") (class "Default")
      (node (ref "SW152") (pin "P$4") (pinfunction "=B_P$4") (pintype "bidirectional"))
      (node (ref "SW164") (pin "P$3") (pinfunction "B_P$3") (pintype "bidirectional"))
    )
    (net (code "69") (name "Net-(SW153-=B)") (class "Default")
      (node (ref "SW153") (pin "P$4") (pinfunction "=B_P$4") (pintype "bidirectional"))
      (node (ref "SW165") (pin "P$3") (pinfunction "B_P$3") (pintype "bidirectional"))
    )
    (net (code "70") (name "Net-(SW154-=B)") (class "Default")
      (node (ref "SW154") (pin "P$4") (pinfunction "=B_P$4") (pintype "bidirectional"))
      (node (ref "SW166") (pin "P$3") (pinfunction "B_P$3") (pintype "bidirectional"))
    )
    (net (code "71") (name "Net-(SW155-=A)") (class "Default")
      (node (ref "SW155") (pin "P$2") (pinfunction "=A_P$2") (pintype "bidirectional"))
      (node (ref "SW167") (pin "P$1") (pinfunction "A_P$1") (pintype "bidirectional"))
    )
    (net (code "72") (name "Net-(SW156-=A)") (class "Default")
      (node (ref "SW156") (pin "P$2") (pinfunction "=A_P$2") (pintype "bidirectional"))
      (node (ref "SW168") (pin "P$1") (pinfunction "A_P$1") (pintype "bidirectional"))
    )
    (net (code "73") (name "Net-(SW157-=A)") (class "Default")
      (node (ref "SW157") (pin "P$2") (pinfunction "=A_P$2") (pintype "bidirectional"))
      (node (ref "SW169") (pin "P$1") (pinfunction "A_P$1") (pintype "bidirectional"))
    )
    (net (code "74") (name "Net-(SW158-=A)") (class "Default")
      (node (ref "SW158") (pin "P$2") (pinfunction "=A_P$2") (pintype "bidirectional"))
      (node (ref "SW170") (pin "P$1") (pinfunction "A_P$1") (pintype "bidirectional"))
    )
    (net (code "75") (name "unconnected-(CN101-Pad1)") (class "Default")
      (node (ref "CN101") (pin "1") (pinfunction "1_1") (pintype "passive"))
    )
    (net (code "76") (name "unconnected-(CN101-Pad3)") (class "Default")
      (node (ref "CN101") (pin "3") (pinfunction "3_3") (pintype "passive"))
    )
    (net (code "77") (name "unconnected-(CN101-Pad11)") (class "Default")
      (node (ref "CN101") (pin "11") (pinfunction "11_11") (pintype "passive"))
    )
    (net (code "78") (name "unconnected-(CN101-Pad12)") (class "Default")
      (node (ref "CN101") (pin "12") (pinfunction "12_12") (pintype "passive"))
    )
    (net (code "79") (name "unconnected-(SW101-=A-PadP$2)") (class "Default")
      (node (ref "SW101") (pin "P$2") (pinfunction "=A_P$2") (pintype "bidirectional"))
    )
    (net (code "80") (name "unconnected-(SW101-B-PadP$3)") (class "Default")
      (node (ref "SW101") (pin "P$3") (pinfunction "B_P$3") (pintype "bidirectional"))
    )
    (net (code "81") (name "unconnected-(SW102-=A-PadP$2)") (class "Default")
      (node (ref "SW102") (pin "P$2") (pinfunction "=A_P$2") (pintype "bidirectional"))
    )
    (net (code "82") (name "unconnected-(SW102-B-PadP$3)") (class "Default")
      (node (ref "SW102") (pin "P$3") (pinfunction "B_P$3") (pintype "bidirectional"))
    )
    (net (code "83") (name "unconnected-(SW103-=A-PadP$2)") (class "Default")
      (node (ref "SW103") (pin "P$2") (pinfunction "=A_P$2") (pintype "bidirectional"))
    )
    (net (code "84") (name "unconnected-(SW103-B-PadP$3)") (class "Default")
      (node (ref "SW103") (pin "P$3") (pinfunction "B_P$3") (pintype "bidirectional"))
    )
    (net (code "85") (name "unconnected-(SW104-=A-PadP$2)") (class "Default")
      (node (ref "SW104") (pin "P$2") (pinfunction "=A_P$2") (pintype "bidirectional"))
    )
    (net (code "86") (name "unconnected-(SW104-B-PadP$3)") (class "Default")
      (node (ref "SW104") (pin "P$3") (pinfunction "B_P$3") (pintype "bidirectional"))
    )
    (net (code "87") (name "unconnected-(SW105-=A-PadP$2)") (class "Default")
      (node (ref "SW105") (pin "P$2") (pinfunction "=A_P$2") (pintype "bidirectional"))
    )
    (net (code "88") (name "unconnected-(SW105-B-PadP$3)") (class "Default")
      (node (ref "SW105") (pin "P$3") (pinfunction "B_P$3") (pintype "bidirectional"))
    )
    (net (code "89") (name "unconnected-(SW106-=A-PadP$2)") (class "Default")
      (node (ref "SW106") (pin "P$2") (pinfunction "=A_P$2") (pintype "bidirectional"))
    )
    (net (code "90") (name "unconnected-(SW106-B-PadP$3)") (class "Default")
      (node (ref "SW106") (pin "P$3") (pinfunction "B_P$3") (pintype "bidirectional"))
    )
    (net (code "91") (name "unconnected-(SW107-=B-PadP$4)") (class "Default")
      (node (ref "SW107") (pin "P$4") (pinfunction "=B_P$4") (pintype "bidirectional"))
    )
    (net (code "92") (name "unconnected-(SW107-A-PadP$1)") (class "Default")
      (node (ref "SW107") (pin "P$1") (pinfunction "A_P$1") (pintype "bidirectional"))
    )
    (net (code "93") (name "unconnected-(SW108-=B-PadP$4)") (class "Default")
      (node (ref "SW108") (pin "P$4") (pinfunction "=B_P$4") (pintype "bidirectional"))
    )
    (net (code "94") (name "unconnected-(SW108-A-PadP$1)") (class "Default")
      (node (ref "SW108") (pin "P$1") (pinfunction "A_P$1") (pintype "bidirectional"))
    )
    (net (code "95") (name "unconnected-(SW109-=B-PadP$4)") (class "Default")
      (node (ref "SW109") (pin "P$4") (pinfunction "=B_P$4") (pintype "bidirectional"))
    )
    (net (code "96") (name "unconnected-(SW109-A-PadP$1)") (class "Default")
      (node (ref "SW109") (pin "P$1") (pinfunction "A_P$1") (pintype "bidirectional"))
    )
    (net (code "97") (name "unconnected-(SW110-=B-PadP$4)") (class "Default")
      (node (ref "SW110") (pin "P$4") (pinfunction "=B_P$4") (pintype "bidirectional"))
    )
    (net (code "98") (name "unconnected-(SW110-A-PadP$1)") (class "Default")
      (node (ref "SW110") (pin "P$1") (pinfunction "A_P$1") (pintype "bidirectional"))
    )
    (net (code "99") (name "unconnected-(SW111-=B-PadP$4)") (class "Default")
      (node (ref "SW111") (pin "P$4") (pinfunction "=B_P$4") (pintype "bidirectional"))
    )
    (net (code "100") (name "unconnected-(SW111-A-PadP$1)") (class "Default")
      (node (ref "SW111") (pin "P$1") (pinfunction "A_P$1") (pintype "bidirectional"))
    )
    (net (code "101") (name "unconnected-(SW112-=B-PadP$4)") (class "Default")
      (node (ref "SW112") (pin "P$4") (pinfunction "=B_P$4") (pintype "bidirectional"))
    )
    (net (code "102") (name "unconnected-(SW112-A-PadP$1)") (class "Default")
      (node (ref "SW112") (pin "P$1") (pinfunction "A_P$1") (pintype "bidirectional"))
    )
    (net (code "103") (name "unconnected-(SW113-=A-PadP$2)") (class "Default")
      (node (ref "SW113") (pin "P$2") (pinfunction "=A_P$2") (pintype "bidirectional"))
    )
    (net (code "104") (name "unconnected-(SW114-=A-PadP$2)") (class "Default")
      (node (ref "SW114") (pin "P$2") (pinfunction "=A_P$2") (pintype "bidirectional"))
    )
    (net (code "105") (name "unconnected-(SW115-=A-PadP$2)") (class "Default")
      (node (ref "SW115") (pin "P$2") (pinfunction "=A_P$2") (pintype "bidirectional"))
    )
    (net (code "106") (name "unconnected-(SW116-=A-PadP$2)") (class "Default")
      (node (ref "SW116") (pin "P$2") (pinfunction "=A_P$2") (pintype "bidirectional"))
    )
    (net (code "107") (name "unconnected-(SW117-=A-PadP$2)") (class "Default")
      (node (ref "SW117") (pin "P$2") (pinfunction "=A_P$2") (pintype "bidirectional"))
    )
    (net (code "108") (name "unconnected-(SW118-=A-PadP$2)") (class "Default")
      (node (ref "SW118") (pin "P$2") (pinfunction "=A_P$2") (pintype "bidirectional"))
    )
    (net (code "109") (name "unconnected-(SW119-=B-PadP$4)") (class "Default")
      (node (ref "SW119") (pin "P$4") (pinfunction "=B_P$4") (pintype "bidirectional"))
    )
    (net (code "110") (name "unconnected-(SW120-=B-PadP$4)") (class "Default")
      (node (ref "SW120") (pin "P$4") (pinfunction "=B_P$4") (pintype "bidirectional"))
    )
    (net (code "111") (name "unconnected-(SW121-=B-PadP$4)") (class "Default")
      (node (ref "SW121") (pin "P$4") (pinfunction "=B_P$4") (pintype "bidirectional"))
    )
    (net (code "112") (name "unconnected-(SW122-=B-PadP$4)") (class "Default")
      (node (ref "SW122") (pin "P$4") (pinfunction "=B_P$4") (pintype "bidirectional"))
    )
    (net (code "113") (name "unconnected-(SW123-=B-PadP$4)") (class "Default")
      (node (ref "SW123") (pin "P$4") (pinfunction "=B_P$4") (pintype "bidirectional"))
    )
    (net (code "114") (name "unconnected-(SW124-=B-PadP$4)") (class "Default")
      (node (ref "SW124") (pin "P$4") (pinfunction "=B_P$4") (pintype "bidirectional"))
    )
    (net (code "115") (name "unconnected-(SW125-=A-PadP$2)") (class "Default")
      (node (ref "SW125") (pin "P$2") (pinfunction "=A_P$2") (pintype "bidirectional"))
    )
    (net (code "116") (name "unconnected-(SW126-=A-PadP$2)") (class "Default")
      (node (ref "SW126") (pin "P$2") (pinfunction "=A_P$2") (pintype "bidirectional"))
    )
    (net (code "117") (name "unconnected-(SW127-=A-PadP$2)") (class "Default")
      (node (ref "SW127") (pin "P$2") (pinfunction "=A_P$2") (pintype "bidirectional"))
    )
    (net (code "118") (name "unconnected-(SW128-=A-PadP$2)") (class "Default")
      (node (ref "SW128") (pin "P$2") (pinfunction "=A_P$2") (pintype "bidirectional"))
    )
    (net (code "119") (name "unconnected-(SW129-=A-PadP$2)") (class "Default")
      (node (ref "SW129") (pin "P$2") (pinfunction "=A_P$2") (pintype "bidirectional"))
    )
    (net (code "120") (name "unconnected-(SW130-=A-PadP$2)") (class "Default")
      (node (ref "SW130") (pin "P$2") (pinfunction "=A_P$2") (pintype "bidirectional"))
    )
    (net (code "121") (name "unconnected-(SW131-=B-PadP$4)") (class "Default")
      (node (ref "SW131") (pin "P$4") (pinfunction "=B_P$4") (pintype "bidirectional"))
    )
    (net (code "122") (name "unconnected-(SW132-=B-PadP$4)") (class "Default")
      (node (ref "SW132") (pin "P$4") (pinfunction "=B_P$4") (pintype "bidirectional"))
    )
    (net (code "123") (name "unconnected-(SW133-=B-PadP$4)") (class "Default")
      (node (ref "SW133") (pin "P$4") (pinfunction "=B_P$4") (pintype "bidirectional"))
    )
    (net (code "124") (name "unconnected-(SW134-=B-PadP$4)") (class "Default")
      (node (ref "SW134") (pin "P$4") (pinfunction "=B_P$4") (pintype "bidirectional"))
    )
    (net (code "125") (name "unconnected-(SW135-=B-PadP$4)") (class "Default")
      (node (ref "SW135") (pin "P$4") (pinfunction "=B_P$4") (pintype "bidirectional"))
    )
    (net (code "126") (name "unconnected-(SW136-=B-PadP$4)") (class "Default")
      (node (ref "SW136") (pin "P$4") (pinfunction "=B_P$4") (pintype "bidirectional"))
    )
    (net (code "127") (name "unconnected-(SW137-=A-PadP$2)") (class "Default")
      (node (ref "SW137") (pin "P$2") (pinfunction "=A_P$2") (pintype "bidirectional"))
    )
    (net (code "128") (name "unconnected-(SW138-=A-PadP$2)") (class "Default")
      (node (ref "SW138") (pin "P$2") (pinfunction "=A_P$2") (pintype "bidirectional"))
    )
    (net (code "129") (name "unconnected-(SW139-=A-PadP$2)") (class "Default")
      (node (ref "SW139") (pin "P$2") (pinfunction "=A_P$2") (pintype "bidirectional"))
    )
    (net (code "130") (name "unconnected-(SW140-=A-PadP$2)") (class "Default")
      (node (ref "SW140") (pin "P$2") (pinfunction "=A_P$2") (pintype "bidirectional"))
    )
    (net (code "131") (name "unconnected-(SW141-=A-PadP$2)") (class "Default")
      (node (ref "SW141") (pin "P$2") (pinfunction "=A_P$2") (pintype "bidirectional"))
    )
    (net (code "132") (name "unconnected-(SW142-=A-PadP$2)") (class "Default")
      (node (ref "SW142") (pin "P$2") (pinfunction "=A_P$2") (pintype "bidirectional"))
    )
    (net (code "133") (name "unconnected-(SW143-=B-PadP$4)") (class "Default")
      (node (ref "SW143") (pin "P$4") (pinfunction "=B_P$4") (pintype "bidirectional"))
    )
    (net (code "134") (name "unconnected-(SW144-=B-PadP$4)") (class "Default")
      (node (ref "SW144") (pin "P$4") (pinfunction "=B_P$4") (pintype "bidirectional"))
    )
    (net (code "135") (name "unconnected-(SW145-=B-PadP$4)") (class "Default")
      (node (ref "SW145") (pin "P$4") (pinfunction "=B_P$4") (pintype "bidirectional"))
    )
    (net (code "136") (name "unconnected-(SW146-=B-PadP$4)") (class "Default")
      (node (ref "SW146") (pin "P$4") (pinfunction "=B_P$4") (pintype "bidirectional"))
    )
    (net (code "137") (name "unconnected-(SW147-=B-PadP$4)") (class "Default")
      (node (ref "SW147") (pin "P$4") (pinfunction "=B_P$4") (pintype "bidirectional"))
    )
    (net (code "138") (name "unconnected-(SW148-=B-PadP$4)") (class "Default")
      (node (ref "SW148") (pin "P$4") (pinfunction "=B_P$4") (pintype "bidirectional"))
    )
    (net (code "139") (name "unconnected-(SW149-=A-PadP$2)") (class "Default")
      (node (ref "SW149") (pin "P$2") (pinfunction "=A_P$2") (pintype "bidirectional"))
    )
    (net (code "140") (name "unconnected-(SW149-=B-PadP$4)") (class "Default")
      (node (ref "SW149") (pin "P$4") (pinfunction "=B_P$4") (pintype "bidirectional"))
    )
    (net (code "141") (name "unconnected-(SW150-=A-PadP$2)") (class "Default")
      (node (ref "SW150") (pin "P$2") (pinfunction "=A_P$2") (pintype "bidirectional"))
    )
    (net (code "142") (name "unconnected-(SW150-=B-PadP$4)") (class "Default")
      (node (ref "SW150") (pin "P$4") (pinfunction "=B_P$4") (pintype "bidirectional"))
    )
    (net (code "143") (name "unconnected-(SW151-=A-PadP$2)") (class "Default")
      (node (ref "SW151") (pin "P$2") (pinfunction "=A_P$2") (pintype "bidirectional"))
    )
    (net (code "144") (name "unconnected-(SW152-=A-PadP$2)") (class "Default")
      (node (ref "SW152") (pin "P$2") (pinfunction "=A_P$2") (pintype "bidirectional"))
    )
    (net (code "145") (name "unconnected-(SW153-=A-PadP$2)") (class "Default")
      (node (ref "SW153") (pin "P$2") (pinfunction "=A_P$2") (pintype "bidirectional"))
    )
    (net (code "146") (name "unconnected-(SW154-=A-PadP$2)") (class "Default")
      (node (ref "SW154") (pin "P$2") (pinfunction "=A_P$2") (pintype "bidirectional"))
    )
    (net (code "147") (name "unconnected-(SW155-=B-PadP$4)") (class "Default")
      (node (ref "SW155") (pin "P$4") (pinfunction "=B_P$4") (pintype "bidirectional"))
    )
    (net (code "148") (name "unconnected-(SW156-=B-PadP$4)") (class "Default")
      (node (ref "SW156") (pin "P$4") (pinfunction "=B_P$4") (pintype "bidirectional"))
    )
    (net (code "149") (name "unconnected-(SW157-=B-PadP$4)") (class "Default")
      (node (ref "SW157") (pin "P$4") (pinfunction "=B_P$4") (pintype "bidirectional"))
    )
    (net (code "150") (name "unconnected-(SW158-=B-PadP$4)") (class "Default")
      (node (ref "SW158") (pin "P$4") (pinfunction "=B_P$4") (pintype "bidirectional"))
    )
    (net (code "151") (name "unconnected-(SW159-=A-PadP$2)") (class "Default")
      (node (ref "SW159") (pin "P$2") (pinfunction "=A_P$2") (pintype "bidirectional"))
    )
    (net (code "152") (name "unconnected-(SW159-=B-PadP$4)") (class "Default")
      (node (ref "SW159") (pin "P$4") (pinfunction "=B_P$4") (pintype "bidirectional"))
    )
    (net (code "153") (name "unconnected-(SW160-=A-PadP$2)") (class "Default")
      (node (ref "SW160") (pin "P$2") (pinfunction "=A_P$2") (pintype "bidirectional"))
    )
    (net (code "154") (name "unconnected-(SW160-=B-PadP$4)") (class "Default")
      (node (ref "SW160") (pin "P$4") (pinfunction "=B_P$4") (pintype "bidirectional"))
    )
    (net (code "155") (name "unconnected-(SW163-=A-PadP$2)") (class "Default")
      (node (ref "SW163") (pin "P$2") (pinfunction "=A_P$2") (pintype "bidirectional"))
    )
    (net (code "156") (name "unconnected-(SW163-=B-PadP$4)") (class "Default")
      (node (ref "SW163") (pin "P$4") (pinfunction "=B_P$4") (pintype "bidirectional"))
    )
    (net (code "157") (name "unconnected-(SW164-=A-PadP$2)") (class "Default")
      (node (ref "SW164") (pin "P$2") (pinfunction "=A_P$2") (pintype "bidirectional"))
    )
    (net (code "158") (name "unconnected-(SW164-=B-PadP$4)") (class "Default")
      (node (ref "SW164") (pin "P$4") (pinfunction "=B_P$4") (pintype "bidirectional"))
    )
    (net (code "159") (name "unconnected-(SW165-=A-PadP$2)") (class "Default")
      (node (ref "SW165") (pin "P$2") (pinfunction "=A_P$2") (pintype "bidirectional"))
    )
    (net (code "160") (name "unconnected-(SW165-=B-PadP$4)") (class "Default")
      (node (ref "SW165") (pin "P$4") (pinfunction "=B_P$4") (pintype "bidirectional"))
    )
    (net (code "161") (name "unconnected-(SW166-=A-PadP$2)") (class "Default")
      (node (ref "SW166") (pin "P$2") (pinfunction "=A_P$2") (pintype "bidirectional"))
    )
    (net (code "162") (name "unconnected-(SW166-=B-PadP$4)") (class "Default")
      (node (ref "SW166") (pin "P$4") (pinfunction "=B_P$4") (pintype "bidirectional"))
    )
    (net (code "163") (name "unconnected-(SW167-=A-PadP$2)") (class "Default")
      (node (ref "SW167") (pin "P$2") (pinfunction "=A_P$2") (pintype "bidirectional"))
    )
    (net (code "164") (name "unconnected-(SW167-=B-PadP$4)") (class "Default")
      (node (ref "SW167") (pin "P$4") (pinfunction "=B_P$4") (pintype "bidirectional"))
    )
    (net (code "165") (name "unconnected-(SW168-=A-PadP$2)") (class "Default")
      (node (ref "SW168") (pin "P$2") (pinfunction "=A_P$2") (pintype "bidirectional"))
    )
    (net (code "166") (name "unconnected-(SW168-=B-PadP$4)") (class "Default")
      (node (ref "SW168") (pin "P$4") (pinfunction "=B_P$4") (pintype "bidirectional"))
    )
    (net (code "167") (name "unconnected-(SW169-=A-PadP$2)") (class "Default")
      (node (ref "SW169") (pin "P$2") (pinfunction "=A_P$2") (pintype "bidirectional"))
    )
    (net (code "168") (name "unconnected-(SW169-=B-PadP$4)") (class "Default")
      (node (ref "SW169") (pin "P$4") (pinfunction "=B_P$4") (pintype "bidirectional"))
    )
    (net (code "169") (name "unconnected-(SW170-=A-PadP$2)") (class "Default")
      (node (ref "SW170") (pin "P$2") (pinfunction "=A_P$2") (pintype "bidirectional"))
    )
    (net (code "170") (name "unconnected-(SW170-=B-PadP$4)") (class "Default")
      (node (ref "SW170") (pin "P$4") (pinfunction "=B_P$4") (pintype "bidirectional"))
    )
  )
)
